# ArtFire_Status.net
KiCad netlist of a schematic drawn in Altium Designer
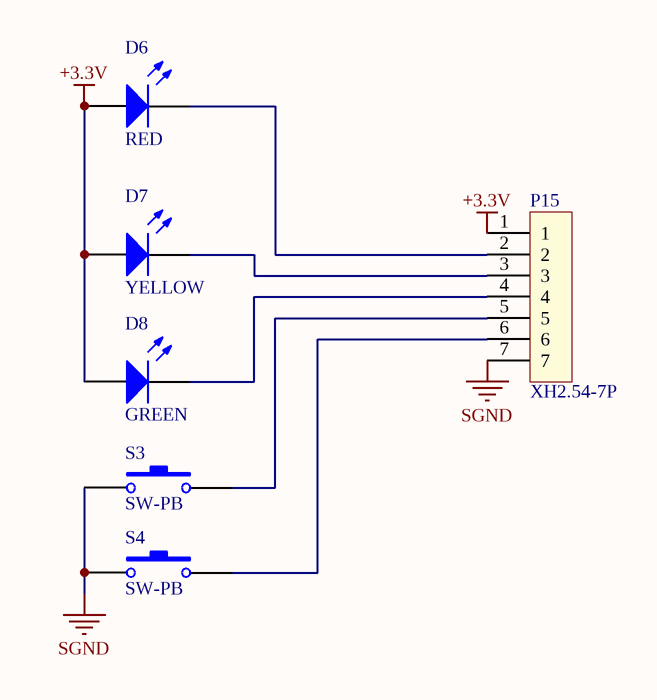
[diagram p0: ArtFire_Status.SchDoc]

(export (version "E")
  (design (tool "Eeschema 10.0.6"))
  (components
    (comp (ref "D6")
      (value "RED")
      (footprint "LED-1")
      (description "Typical RED GaAs LED")
      (fields (field (name "PUBLISHER") "Altium Limited"))
      (libsource (lib "Miscellaneous Devices") (part "LED1"))
    )
    (comp (ref "D7")
      (value "YELLOW")
      (footprint "LED-1")
      (description "Typical RED GaAs LED")
      (fields (field (name "PUBLISHER") "Altium Limited"))
      (libsource (lib "Miscellaneous Devices") (part "LED1"))
    )
    (comp (ref "D8")
      (value "GREEN")
      (footprint "LED-1")
      (description "Typical RED GaAs LED")
      (fields (field (name "PUBLISHER") "Altium Limited"))
      (libsource (lib "Miscellaneous Devices") (part "LED1"))
    )
    (comp (ref "P15")
      (value "XH2.54-7P")
      (footprint "XH2.54-7P")
      (libsource (lib "XH2.54") (part "XH2.54-7P"))
    )
    (comp (ref "S3")
      (value "SW-PB")
      (footprint "KEY_B")
      (description "Switch")
      (fields (field (name "PUBLISHER") "Altium Limited"))
      (libsource (lib "Miscellaneous Devices") (part "SW-PB"))
    )
    (comp (ref "S4")
      (value "SW-PB")
      (footprint "KEY_B")
      (description "Switch")
      (fields (field (name "PUBLISHER") "Altium Limited"))
      (libsource (lib "Miscellaneous Devices") (part "SW-PB"))
    )
  )
  (nets
    (net (code "1") (name "+3.3V") (class "Default")
      (node (ref "D6") (pin "1") (pinfunction "A_1") (pintype "passive"))
      (node (ref "D7") (pin "1") (pinfunction "A_1") (pintype "passive"))
      (node (ref "D8") (pin "1") (pinfunction "A_1") (pintype "passive"))
      (node (ref "P15") (pin "1") (pinfunction "1_1") (pintype "passive"))
    )
    (net (code "2") (name "Net-(D6-K)") (class "Default")
      (node (ref "D6") (pin "2") (pinfunction "K_2") (pintype "passive"))
      (node (ref "P15") (pin "2") (pinfunction "2_2") (pintype "passive"))
    )
    (net (code "3") (name "Net-(D7-K)") (class "Default")
      (node (ref "D7") (pin "2") (pinfunction "K_2") (pintype "passive"))
      (node (ref "P15") (pin "3") (pinfunction "3_3") (pintype "passive"))
    )
    (net (code "4") (name "Net-(D8-K)") (class "Default")
      (node (ref "D8") (pin "2") (pinfunction "K_2") (pintype "passive"))
      (node (ref "P15") (pin "4") (pinfunction "4_4") (pintype "passive"))
    )
    (net (code "5") (name "Net-(P15-Pad5)") (class "Default")
      (node (ref "P15") (pin "5") (pinfunction "5_5") (pintype "passive"))
      (node (ref "S3") (pin "2") (pinfunction "2_2") (pintype "passive"))
    )
    (net (code "6") (name "Net-(P15-Pad6)") (class "Default")
      (node (ref "P15") (pin "6") (pinfunction "6_6") (pintype "passive"))
      (node (ref "S4") (pin "2") (pinfunction "2_2") (pintype "passive"))
    )
    (net (code "7") (name "SGND") (class "Default")
      (node (ref "P15") (pin "7") (pinfunction "7_7") (pintype "passive"))
      (node (ref "S3") (pin "1") (pinfunction "1_1") (pintype "passive"))
      (node (ref "S4") (pin "1") (pinfunction "1_1") (pintype "passive"))
    )
  )
)
